# Microprocessor_PIC18F46K80.net
KiCad netlist of a schematic drawn in Altium Designer
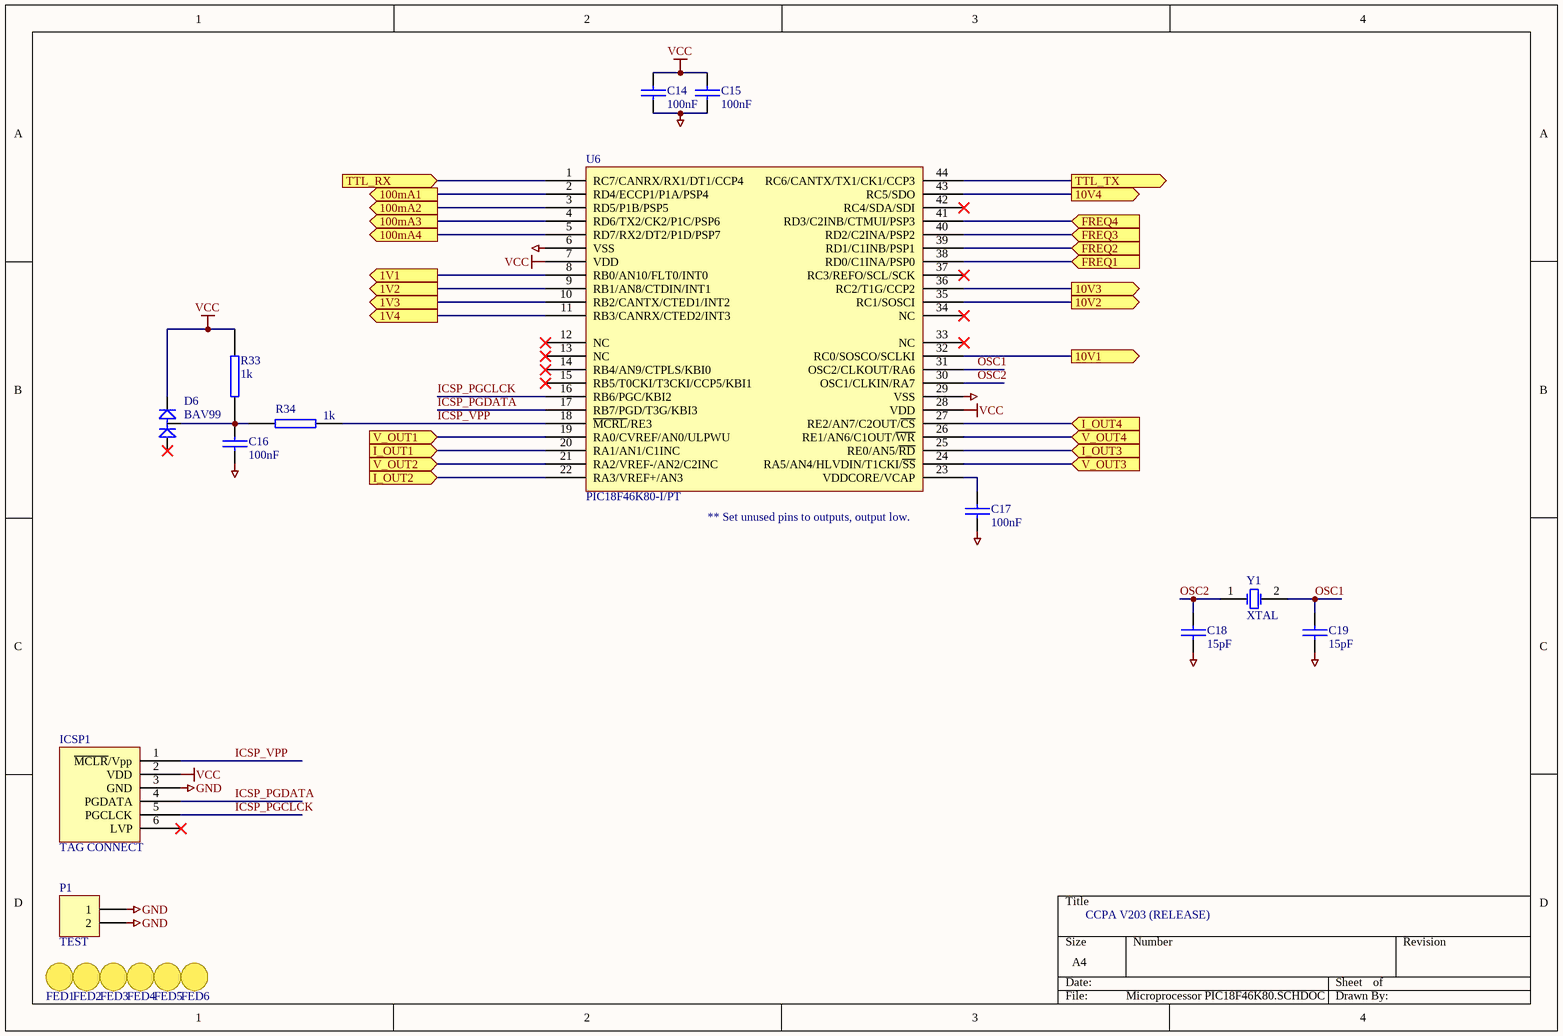
[diagram p0: Microprocessor PIC18F46K80.SCHDOC]

(export (version "E")
  (design (tool "Eeschema 10.0.6"))
  (components
    (comp (ref "C14")
      (value "100nF")
      (footprint "CAP (3D) - 0603")
      (description "CAPACITOR SMD 0402")
      (fields (field (name "MOUSER PART NO.") "81-GRM155R61C104KA8D") (field (name "MANUFACTURER") "Murata"))
      (libsource (lib "401 CCPA") (part "CAP"))
    )
    (comp (ref "C15")
      (value "100nF")
      (footprint "CAP (3D) - 0603")
      (description "CAPACITOR SMD 0402")
      (fields (field (name "MOUSER PART NO.") "81-GRM155R61C104KA8D") (field (name "MANUFACTURER") "Murata"))
      (libsource (lib "401 CCPA") (part "CAP"))
    )
    (comp (ref "C16")
      (value "100nF")
      (footprint "CAP (3D) - 0603")
      (description "CAPACITOR SMD 0402")
      (fields (field (name "MOUSER PART NO.") "81-GRM155R61C104KA8D") (field (name "MANUFACTURER") "Murata"))
      (libsource (lib "401 CCPA") (part "CAP"))
    )
    (comp (ref "C17")
      (value "100nF")
      (footprint "CAP (3D) - 0603")
      (description "CAPACITOR SMD 0402")
      (fields (field (name "MOUSER PART NO.") "81-GRM155R61C104KA8D") (field (name "MANUFACTURER") "Murata"))
      (libsource (lib "401 CCPA") (part "CAP"))
    )
    (comp (ref "C18")
      (value "15pF")
      (footprint "CAP (3D) - 0603")
      (description "CAPACITOR SMD 0402")
      (fields (field (name "MOUSER PART NO.") "140-CC504N150J-RC") (field (name "MANUFACTURER") "Xicon"))
      (libsource (lib "401 CCPA") (part "CAP"))
    )
    (comp (ref "C19")
      (value "15pF")
      (footprint "CAP (3D) - 0603")
      (description "CAPACITOR SMD 0402")
      (fields (field (name "MOUSER PART NO.") "140-CC504N150J-RC") (field (name "MANUFACTURER") "Xicon"))
      (libsource (lib "401 CCPA") (part "CAP"))
    )
    (comp (ref "D6")
      (value "BAV99")
      (footprint "SOT23-3L")
      (description "DUAL DIODE, BAV99")
      (fields
        (field (name "MOUSER PART NO.") "771-BAV99/T3")
        (field (name "MANUFACTURER") "FAIRCHILD SEMICONDUCTOR")
      )
      (libsource (lib "401 CCPA") (part "BAV99"))
    )
    (comp (ref "FED1")
      (value "Feducial")
      (footprint "Feducial")
      (fields (field (name "MANUFACTURER") "N/A - PCB ARTWORK"))
      (libsource (lib "401 CCPA") (part "Feducial"))
    )
    (comp (ref "FED2")
      (value "Feducial")
      (footprint "Feducial")
      (fields (field (name "MANUFACTURER") "N/A - PCB ARTWORK"))
      (libsource (lib "401 CCPA") (part "Feducial"))
    )
    (comp (ref "FED3")
      (value "Feducial")
      (footprint "Feducial")
      (fields (field (name "MANUFACTURER") "N/A - PCB ARTWORK"))
      (libsource (lib "401 CCPA") (part "Feducial"))
    )
    (comp (ref "FED4")
      (value "Feducial")
      (footprint "Feducial")
      (fields (field (name "MANUFACTURER") "N/A - PCB ARTWORK"))
      (libsource (lib "401 CCPA") (part "Feducial"))
    )
    (comp (ref "FED5")
      (value "Feducial")
      (footprint "Feducial")
      (fields (field (name "MANUFACTURER") "N/A - PCB ARTWORK"))
      (libsource (lib "401 CCPA") (part "Feducial"))
    )
    (comp (ref "FED6")
      (value "Feducial")
      (footprint "Feducial")
      (fields (field (name "MANUFACTURER") "N/A - PCB ARTWORK"))
      (libsource (lib "401 CCPA") (part "Feducial"))
    )
    (comp (ref "ICSP1")
      (value "TAG CONNECT")
      (footprint "ICSP - TAG CONNECT TYPE2")
      (fields (field (name "MANUFACTURER") "N/A - PCB ARTWORK"))
      (libsource (lib "I2C PENDANT") (part "ICSP - TAG CONNECT"))
    )
    (comp (ref "P1")
      (value "TEST")
      (footprint "HDR1X2")
      (description "Header, 2-Pin")
      (fields
        (field (name "MANUFACTURER") "Bourns")
        (field (name "MANUFACTURER PART NO.") "CR0603-FX-5900ELF")
      )
      (libsource (lib "Miscellaneous Connectors") (part "Header 2"))
    )
    (comp (ref "R33")
      (value "1k")
      (footprint "RES (3D) - 0603")
      (description "RESISTOR SMD 0603 10k")
      (fields (field (name "MOUSER PART NO.") "652-CR0603-JW-102ELF") (field (name "MANUFACTURER") "Bourns"))
      (libsource (lib "NASCO Resistors") (part "RES SMD 0603 10k"))
    )
    (comp (ref "R34")
      (value "1k")
      (footprint "RES (3D) - 0603")
      (description "RESISTOR SMD 0603")
      (fields
        (field (name "MOUSER PART NO.") "652-CR0603-JW-102ELF")
        (field (name "FARNELL PART NO.") "9331700")
      )
      (libsource (lib "NASCO Resistors") (part "RES SMD 0603 100R"))
    )
    (comp (ref "U6")
      (value "PIC18F46K80-I/PT")
      (footprint "TQFP44_L")
      (description "PIC18F4XK80-I/PT")
      (fields
        (field (name "MANUFACTURER") "MICROCHIP")
        (field (name "MOUSER PART NO.") "579-PIC18F46K80-I/PT")
      )
      (libsource (lib "parts library") (part "PIC18F4XK80-I/PT"))
    )
    (comp (ref "Y1")
      (value "XTAL")
      (footprint "HC49/4H_SMX")
      (description "Crystal Oscillator")
      (fields (field (name "MANUFACTURER") "ECS") (field (name "MANUFACTURER PART NO.") "ECS-160-20-5PX-TR"))
      (libsource (lib "Miscellaneous Devices") (part "XTAL"))
    )
  )
  (nets
    (net (code "1") (name "/1V1") (class "Default")
      (node (ref "U6") (pin "8") (pinfunction "RB0/AN10/FLT0/INT0_8") (pintype "passive"))
    )
    (net (code "2") (name "/1V2") (class "Default")
      (node (ref "U6") (pin "9") (pinfunction "RB1/AN8/CTDIN/INT1_9") (pintype "passive"))
    )
    (net (code "3") (name "/1V3") (class "Default")
      (node (ref "U6") (pin "10") (pinfunction "RB2/CANTX/CTED1/INT2_10") (pintype "passive"))
    )
    (net (code "4") (name "/1V4") (class "Default")
      (node (ref "U6") (pin "11") (pinfunction "RB3/CANRX/CTED2/INT3_11") (pintype "passive"))
    )
    (net (code "5") (name "/10V1") (class "Default")
      (node (ref "U6") (pin "32") (pinfunction "RC0/SOSCO/SCLKI_32") (pintype "passive"))
    )
    (net (code "6") (name "/10V2") (class "Default")
      (node (ref "U6") (pin "35") (pinfunction "RC1/SOSCI_35") (pintype "passive"))
    )
    (net (code "7") (name "/10V3") (class "Default")
      (node (ref "U6") (pin "36") (pinfunction "RC2/T1G/CCP2_36") (pintype "passive"))
    )
    (net (code "8") (name "/10V4") (class "Default")
      (node (ref "U6") (pin "43") (pinfunction "RC5/SDO_43") (pintype "passive"))
    )
    (net (code "9") (name "/100mA1") (class "Default")
      (node (ref "U6") (pin "2") (pinfunction "RD4/ECCP1/P1A/PSP4_2") (pintype "passive"))
    )
    (net (code "10") (name "/100mA2") (class "Default")
      (node (ref "U6") (pin "3") (pinfunction "RD5/P1B/PSP5_3") (pintype "passive"))
    )
    (net (code "11") (name "/100mA3") (class "Default")
      (node (ref "U6") (pin "4") (pinfunction "RD6/TX2/CK2/P1C/PSP6_4") (pintype "passive"))
    )
    (net (code "12") (name "/100mA4") (class "Default")
      (node (ref "U6") (pin "5") (pinfunction "RD7/RX2/DT2/P1D/PSP7_5") (pintype "passive"))
    )
    (net (code "13") (name "/FREQ1") (class "Default")
      (node (ref "U6") (pin "38") (pinfunction "RD0/C1INA/PSP0_38") (pintype "passive"))
    )
    (net (code "14") (name "/FREQ2") (class "Default")
      (node (ref "U6") (pin "39") (pinfunction "RD1/C1INB/PSP1_39") (pintype "passive"))
    )
    (net (code "15") (name "/FREQ3") (class "Default")
      (node (ref "U6") (pin "40") (pinfunction "RD2/C2INA/PSP2_40") (pintype "passive"))
    )
    (net (code "16") (name "/FREQ4") (class "Default")
      (node (ref "U6") (pin "41") (pinfunction "RD3/C2INB/CTMUI/PSP3_41") (pintype "passive"))
    )
    (net (code "17") (name "/ICSP_PGCLCK") (class "Default")
      (node (ref "ICSP1") (pin "5") (pinfunction "PGCLCK_5") (pintype "passive"))
      (node (ref "U6") (pin "16") (pinfunction "RB6/PGC/KBI2_16") (pintype "passive"))
    )
    (net (code "18") (name "/ICSP_PGDATA") (class "Default")
      (node (ref "ICSP1") (pin "4") (pinfunction "PGDATA_4") (pintype "passive"))
      (node (ref "U6") (pin "17") (pinfunction "RB7/PGD/T3G/KBI3_17") (pintype "passive"))
    )
    (net (code "19") (name "/ICSP_VPP") (class "Default")
      (node (ref "ICSP1") (pin "1") (pinfunction "~{MCLR}/Vpp_1") (pintype "passive"))
      (node (ref "R34") (pin "2") (pinfunction "2_2") (pintype "passive"))
      (node (ref "U6") (pin "18") (pinfunction "~{MCRL}/RE3_18") (pintype "passive"))
    )
    (net (code "20") (name "/I_OUT1") (class "Default")
      (node (ref "U6") (pin "20") (pinfunction "RA1/AN1/C1INC_20") (pintype "passive"))
    )
    (net (code "21") (name "/I_OUT2") (class "Default")
      (node (ref "U6") (pin "22") (pinfunction "RA3/VREF+/AN3_22") (pintype "passive"))
    )
    (net (code "22") (name "/I_OUT3") (class "Default")
      (node (ref "U6") (pin "25") (pinfunction "RE0/AN5/~{RD}_25") (pintype "passive"))
    )
    (net (code "23") (name "/I_OUT4") (class "Default")
      (node (ref "U6") (pin "27") (pinfunction "RE2/AN7/C2OUT/~{CS}_27") (pintype "passive"))
    )
    (net (code "24") (name "/OSC1") (class "Default")
      (node (ref "C19") (pin "1") (pinfunction "1_1") (pintype "passive"))
      (node (ref "U6") (pin "31") (pinfunction "OSC2/CLKOUT/RA6_31") (pintype "passive"))
      (node (ref "Y1") (pin "2") (pinfunction "OSC2_2") (pintype "passive"))
    )
    (net (code "25") (name "/OSC2") (class "Default")
      (node (ref "C18") (pin "1") (pinfunction "1_1") (pintype "passive"))
      (node (ref "U6") (pin "30") (pinfunction "OSC1/CLKIN/RA7_30") (pintype "passive"))
      (node (ref "Y1") (pin "1") (pinfunction "OSC1_1") (pintype "passive"))
    )
    (net (code "26") (name "/TTL_RX") (class "Default")
      (node (ref "U6") (pin "1") (pinfunction "RC7/CANRX/RX1/DT1/CCP4_1") (pintype "passive"))
    )
    (net (code "27") (name "/TTL_TX") (class "Default")
      (node (ref "U6") (pin "44") (pinfunction "RC6/CANTX/TX1/CK1/CCP3_44") (pintype "passive"))
    )
    (net (code "28") (name "/V_OUT1") (class "Default")
      (node (ref "U6") (pin "19") (pinfunction "RA0/CVREF/AN0/ULPWU_19") (pintype "passive"))
    )
    (net (code "29") (name "/V_OUT2") (class "Default")
      (node (ref "U6") (pin "21") (pinfunction "RA2/VREF-/AN2/C2INC_21") (pintype "passive"))
    )
    (net (code "30") (name "/V_OUT3") (class "Default")
      (node (ref "U6") (pin "24") (pinfunction "RA5/AN4/HLVDIN/T1CKI/~{SS}_24") (pintype "passive"))
    )
    (net (code "31") (name "/V_OUT4") (class "Default")
      (node (ref "U6") (pin "26") (pinfunction "RE1/AN6/C1OUT/~{WR}_26") (pintype "passive"))
    )
    (net (code "32") (name "GND") (class "Default")
      (node (ref "C14") (pin "2") (pinfunction "2_2") (pintype "passive"))
      (node (ref "C15") (pin "2") (pinfunction "2_2") (pintype "passive"))
      (node (ref "C16") (pin "2") (pinfunction "2_2") (pintype "passive"))
      (node (ref "C17") (pin "2") (pinfunction "2_2") (pintype "passive"))
      (node (ref "C18") (pin "2") (pinfunction "2_2") (pintype "passive"))
      (node (ref "C19") (pin "2") (pinfunction "2_2") (pintype "passive"))
      (node (ref "ICSP1") (pin "3") (pinfunction "GND_3") (pintype "passive"))
      (node (ref "P1") (pin "1") (pinfunction "1_1") (pintype "passive"))
      (node (ref "P1") (pin "2") (pinfunction "2_2") (pintype "passive"))
      (node (ref "U6") (pin "29") (pinfunction "VSS_29") (pintype "passive"))
      (node (ref "U6") (pin "6") (pinfunction "VSS_6") (pintype "passive"))
    )
    (net (code "33") (name "Net-(D6-C1{slash}A2)") (class "Default")
      (node (ref "C16") (pin "1") (pinfunction "1_1") (pintype "passive"))
      (node (ref "D6") (pin "3") (pinfunction "C1/A2_3") (pintype "passive"))
      (node (ref "R33") (pin "2") (pinfunction "2_2") (pintype "passive"))
      (node (ref "R34") (pin "1") (pinfunction "1_1") (pintype "passive"))
    )
    (net (code "34") (name "Net-(U6-VDDCORE{slash}VCAP)") (class "Default")
      (node (ref "C17") (pin "1") (pinfunction "1_1") (pintype "passive"))
      (node (ref "U6") (pin "23") (pinfunction "VDDCORE/VCAP_23") (pintype "passive"))
    )
    (net (code "35") (name "VCC") (class "Default")
      (node (ref "C14") (pin "1") (pinfunction "1_1") (pintype "passive"))
      (node (ref "C15") (pin "1") (pinfunction "1_1") (pintype "passive"))
      (node (ref "D6") (pin "2") (pinfunction "C2_2") (pintype "passive"))
      (node (ref "ICSP1") (pin "2") (pinfunction "VDD_2") (pintype "passive"))
      (node (ref "R33") (pin "1") (pinfunction "1_1") (pintype "passive"))
      (node (ref "U6") (pin "28") (pinfunction "VDD_28") (pintype "passive"))
      (node (ref "U6") (pin "7") (pinfunction "VDD_7") (pintype "passive"))
    )
    (net (code "36") (name "unconnected-(D6-A1-Pad1)") (class "Default")
      (node (ref "D6") (pin "1") (pinfunction "A1_1") (pintype "passive+no_connect"))
    )
    (net (code "37") (name "unconnected-(ICSP1-LVP-Pad6)") (class "Default")
      (node (ref "ICSP1") (pin "6") (pinfunction "LVP_6") (pintype "passive+no_connect"))
    )
    (net (code "38") (name "unconnected-(U6-NC-Pad12)") (class "Default")
      (node (ref "U6") (pin "12") (pinfunction "NC_12") (pintype "passive+no_connect"))
    )
    (net (code "39") (name "unconnected-(U6-NC-Pad13)") (class "Default")
      (node (ref "U6") (pin "13") (pinfunction "NC_13") (pintype "passive+no_connect"))
    )
    (net (code "40") (name "unconnected-(U6-NC-Pad33)") (class "Default")
      (node (ref "U6") (pin "33") (pinfunction "NC_33") (pintype "passive+no_connect"))
    )
    (net (code "41") (name "unconnected-(U6-NC-Pad34)") (class "Default")
      (node (ref "U6") (pin "34") (pinfunction "NC_34") (pintype "passive+no_connect"))
    )
    (net (code "42") (name "unconnected-(U6-RB4{slash}AN9{slash}CTPLS{slash}KBI0-Pad14)") (class "Default")
      (node (ref "U6") (pin "14") (pinfunction "RB4/AN9/CTPLS/KBI0_14") (pintype "passive+no_connect"))
    )
    (net (code "43") (name "unconnected-(U6-RB5{slash}T0CKI{slash}T3CKI{slash}CCP5{slash}KBI1-Pad15)") (class "Default")
      (node (ref "U6") (pin "15") (pinfunction "RB5/T0CKI/T3CKI/CCP5/KBI1_15") (pintype "passive+no_connect"))
    )
    (net (code "44") (name "unconnected-(U6-RC3{slash}REFO{slash}SCL{slash}SCK-Pad37)") (class "Default")
      (node (ref "U6") (pin "37") (pinfunction "RC3/REFO/SCL/SCK_37") (pintype "passive+no_connect"))
    )
    (net (code "45") (name "unconnected-(U6-RC4{slash}SDA{slash}SDI-Pad42)") (class "Default")
      (node (ref "U6") (pin "42") (pinfunction "RC4/SDA/SDI_42") (pintype "passive+no_connect"))
    )
  )
)
